# HV_SNS_V0_1.net
KiCad netlist of a schematic drawn in EAGLE
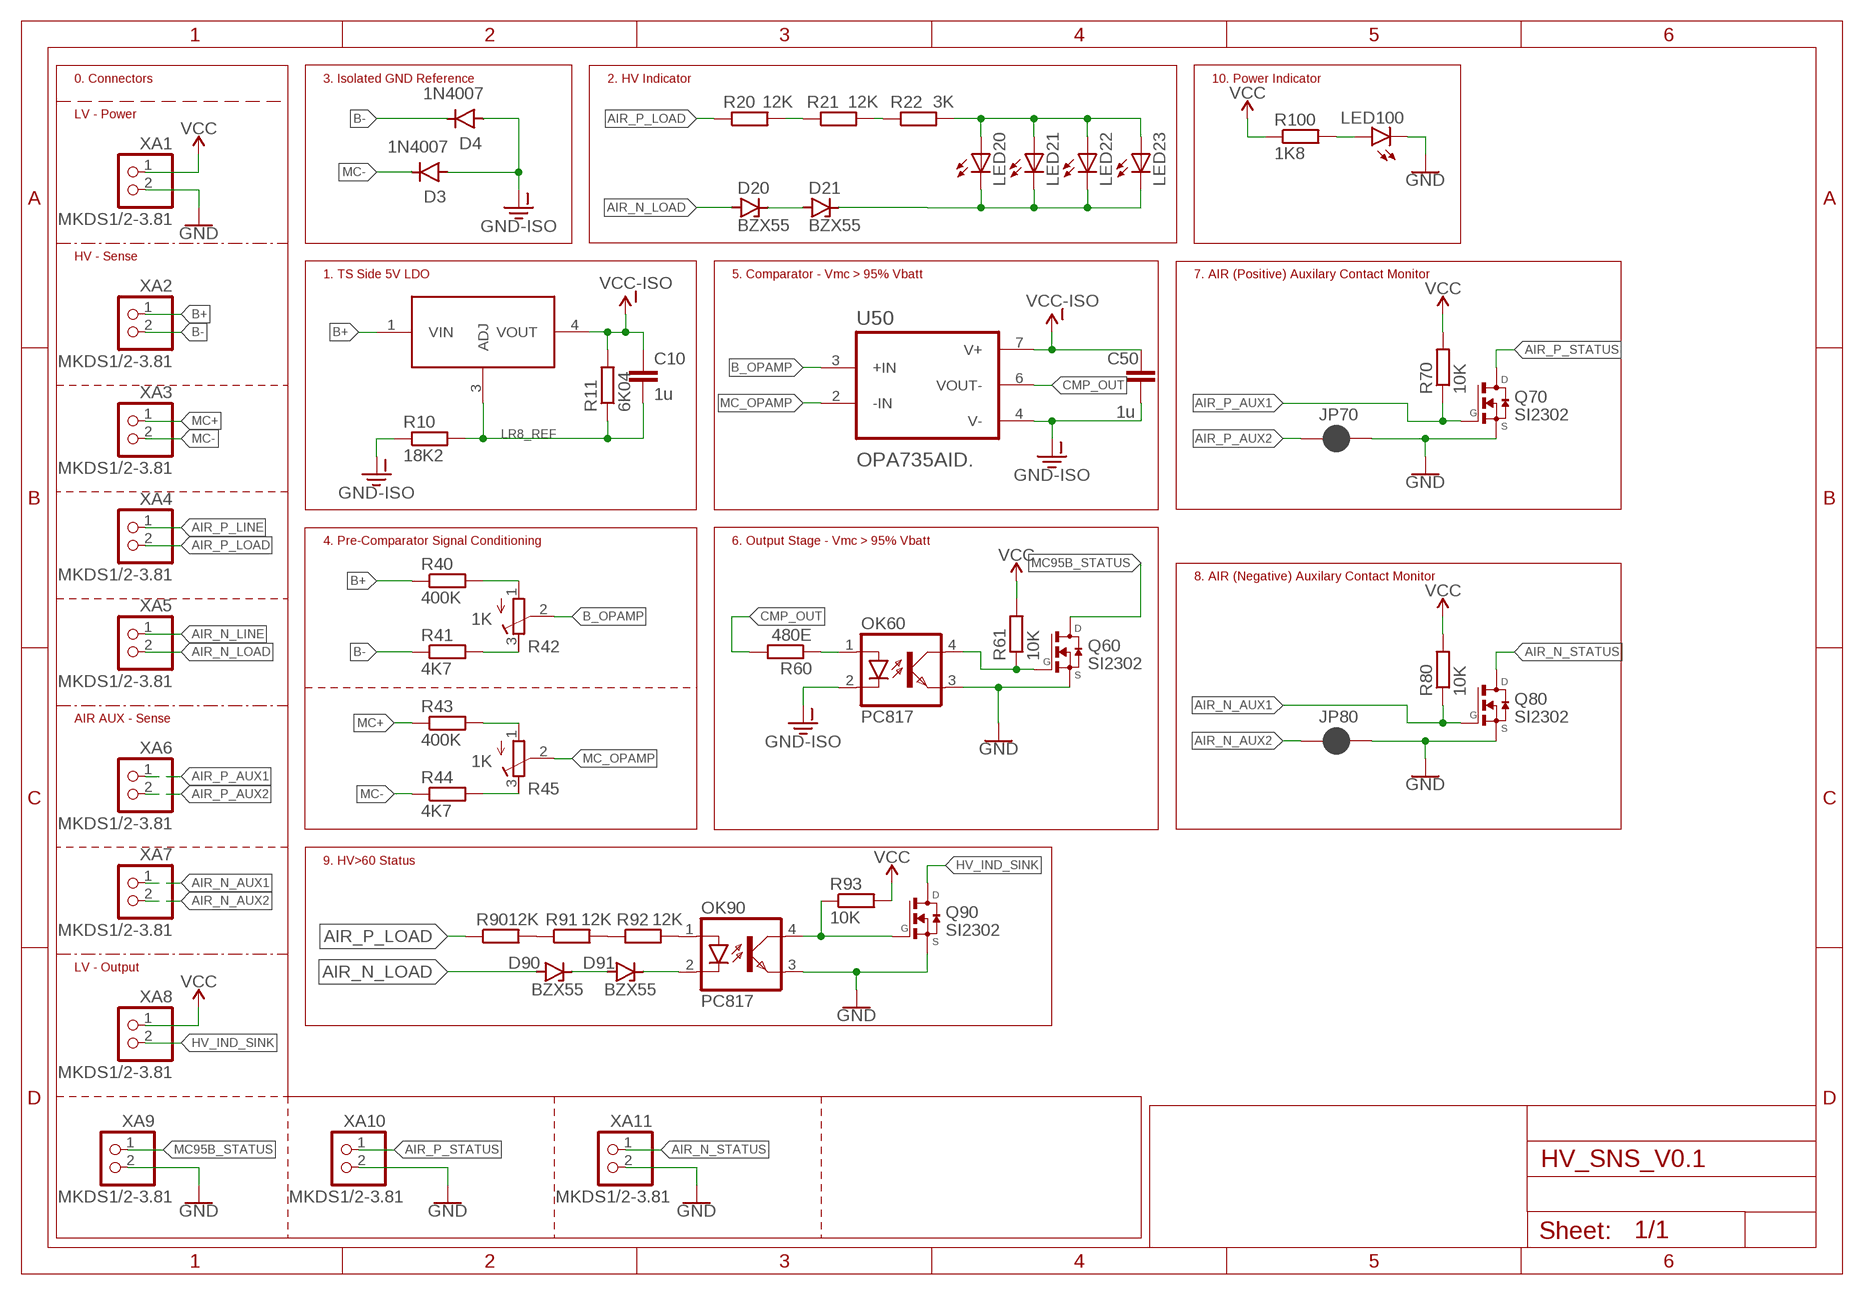
[diagram p0: schematic, sheet 1]

(export (version "E")
  (design (tool "Eeschema 10.0.6"))
  (components
    (comp (ref "C10")
      (value "1u")
      (footprint "eagle-import:C0805")
      (libsource (lib "eagle-import") (part "C-EUC0805"))
    )
    (comp (ref "C50")
      (value "1u")
      (footprint "eagle-import:C0805")
      (libsource (lib "eagle-import") (part "C-EUC0805"))
    )
    (comp (ref "D3")
      (value "1N4007")
      (footprint "eagle-import:DO-41")
      (fields
        (field (name "DIGIKEY_PART_NUMBER") "1N4007MSCT-ND")
        (field (name "MANUFACTURER") "Micro Commercial Co")
        (field (name "CREATED_BY") "PCBLayout.com")
      )
      (libsource (lib "eagle-import") (part "1N4007"))
    )
    (comp (ref "D4")
      (value "1N4007")
      (footprint "eagle-import:DO-41")
      (fields
        (field (name "DIGIKEY_PART_NUMBER") "1N4007MSCT-ND")
        (field (name "MANUFACTURER") "Micro Commercial Co")
        (field (name "CREATED_BY") "PCBLayout.com")
      )
      (libsource (lib "eagle-import") (part "1N4007"))
    )
    (comp (ref "D20")
      (value "BZX55")
      (footprint "eagle-import:DO35Z10")
      (libsource (lib "eagle-import") (part "BZX55"))
    )
    (comp (ref "D21")
      (value "BZX55")
      (footprint "eagle-import:DO35Z10")
      (libsource (lib "eagle-import") (part "BZX55"))
    )
    (comp (ref "D90")
      (value "BZX55")
      (footprint "eagle-import:DO35Z10")
      (libsource (lib "eagle-import") (part "BZX55"))
    )
    (comp (ref "D91")
      (value "BZX55")
      (footprint "eagle-import:DO35Z10")
      (libsource (lib "eagle-import") (part "BZX55"))
    )
    (comp (ref "JP70")
      (value "JUMPER-SMT_2_NC_PASTE_SILK")
      (footprint "eagle-import:SMT-JUMPER_2_NC_PASTE_SILK")
      (libsource (lib "eagle-import") (part "JUMPER-SMT_2_NC_PASTE_SILK"))
    )
    (comp (ref "JP80")
      (value "JUMPER-SMT_2_NC_PASTE_SILK")
      (footprint "eagle-import:SMT-JUMPER_2_NC_PASTE_SILK")
      (libsource (lib "eagle-import") (part "JUMPER-SMT_2_NC_PASTE_SILK"))
    )
    (comp (ref "LED20")
      (value "LED5MM")
      (footprint "eagle-import:LED5MM")
      (libsource (lib "eagle-import") (part "LED5MM"))
    )
    (comp (ref "LED21")
      (value "LED5MM")
      (footprint "eagle-import:LED5MM")
      (libsource (lib "eagle-import") (part "LED5MM"))
    )
    (comp (ref "LED22")
      (value "LED5MM")
      (footprint "eagle-import:LED5MM")
      (libsource (lib "eagle-import") (part "LED5MM"))
    )
    (comp (ref "LED23")
      (value "LED5MM")
      (footprint "eagle-import:LED5MM")
      (libsource (lib "eagle-import") (part "LED5MM"))
    )
    (comp (ref "LED100")
      (value "LEDCHIP-LED0805")
      (footprint "eagle-import:CHIP-LED0805")
      (libsource (lib "eagle-import") (part "led_259_LEDCHIP-LED0805"))
    )
    (comp (ref "OK60")
      (value "PC817")
      (footprint "eagle-import:DIL04")
      (fields (field (name "MPN") "PC817X4J000F"))
      (libsource (lib "eagle-import") (part "PC817"))
    )
    (comp (ref "OK90")
      (value "PC817")
      (footprint "eagle-import:DIL04")
      (fields (field (name "MPN") "PC817X4J000F"))
      (libsource (lib "eagle-import") (part "PC817"))
    )
    (comp (ref "Q60")
      (value "SI2302")
      (footprint "eagle-import:SOT23")
      (fields (field (name "MF") "Vishay Siliconix"))
      (libsource (lib "eagle-import") (part "SI2302"))
    )
    (comp (ref "Q70")
      (value "SI2302")
      (footprint "eagle-import:SOT23")
      (fields (field (name "MF") "Vishay Siliconix"))
      (libsource (lib "eagle-import") (part "SI2302"))
    )
    (comp (ref "Q80")
      (value "SI2302")
      (footprint "eagle-import:SOT23")
      (fields (field (name "MF") "Vishay Siliconix"))
      (libsource (lib "eagle-import") (part "SI2302"))
    )
    (comp (ref "Q90")
      (value "SI2302")
      (footprint "eagle-import:SOT23")
      (fields (field (name "MF") "Vishay Siliconix"))
      (libsource (lib "eagle-import") (part "SI2302"))
    )
    (comp (ref "R10")
      (value "18K2")
      (footprint "eagle-import:R0805")
      (libsource (lib "eagle-import") (part "R-EU_R0805"))
    )
    (comp (ref "R11")
      (value "6K04")
      (footprint "eagle-import:R0805")
      (libsource (lib "eagle-import") (part "R-EU_R0805"))
    )
    (comp (ref "R20")
      (value "12K")
      (footprint "eagle-import:0207_10")
      (libsource (lib "eagle-import") (part "R-EU_0207/10"))
    )
    (comp (ref "R21")
      (value "12K")
      (footprint "eagle-import:0207_10")
      (libsource (lib "eagle-import") (part "R-EU_0207/10"))
    )
    (comp (ref "R22")
      (value "3K")
      (footprint "eagle-import:0207_10")
      (libsource (lib "eagle-import") (part "R-EU_0207/10"))
    )
    (comp (ref "R40")
      (value "400K")
      (footprint "eagle-import:0207_10")
      (libsource (lib "eagle-import") (part "R-EU_0207/10"))
    )
    (comp (ref "R41")
      (value "4K7")
      (footprint "eagle-import:0207_10")
      (libsource (lib "eagle-import") (part "R-EU_0207/10"))
    )
    (comp (ref "R42")
      (value "1K")
      (footprint "eagle-import:RTRIM3296W")
      (libsource (lib "eagle-import") (part "R-TRIMM3296W"))
    )
    (comp (ref "R43")
      (value "400K")
      (footprint "eagle-import:0207_10")
      (libsource (lib "eagle-import") (part "R-EU_0207/10"))
    )
    (comp (ref "R44")
      (value "4K7")
      (footprint "eagle-import:0207_10")
      (libsource (lib "eagle-import") (part "R-EU_0207/10"))
    )
    (comp (ref "R45")
      (value "1K")
      (footprint "eagle-import:RTRIM3296W")
      (libsource (lib "eagle-import") (part "R-TRIMM3296W"))
    )
    (comp (ref "R60")
      (value "480E")
      (footprint "eagle-import:R0805")
      (libsource (lib "eagle-import") (part "R-EU_R0805"))
    )
    (comp (ref "R61")
      (value "10K")
      (footprint "eagle-import:R0805")
      (libsource (lib "eagle-import") (part "R-EU_R0805"))
    )
    (comp (ref "R70")
      (value "10K")
      (footprint "eagle-import:R0805")
      (libsource (lib "eagle-import") (part "R-EU_R0805"))
    )
    (comp (ref "R80")
      (value "10K")
      (footprint "eagle-import:R0805")
      (libsource (lib "eagle-import") (part "R-EU_R0805"))
    )
    (comp (ref "R90")
      (value "12K")
      (footprint "eagle-import:0207_10")
      (libsource (lib "eagle-import") (part "R-EU_0207/10"))
    )
    (comp (ref "R91")
      (value "12K")
      (footprint "eagle-import:0207_10")
      (libsource (lib "eagle-import") (part "R-EU_0207/10"))
    )
    (comp (ref "R92")
      (value "12K")
      (footprint "eagle-import:0207_10")
      (libsource (lib "eagle-import") (part "R-EU_0207/10"))
    )
    (comp (ref "R93")
      (value "10K")
      (footprint "eagle-import:R0805")
      (libsource (lib "eagle-import") (part "R-EU_R0805"))
    )
    (comp (ref "R100")
      (value "1K8")
      (footprint "eagle-import:R0805")
      (libsource (lib "eagle-import") (part "R-EU_R0805"))
    )
    (comp (ref "U10")
      (value "LR8K4-G")
      (footprint "eagle-import:PMX42_DPAK")
      (libsource (lib "eagle-import") (part "LR8K4-G"))
    )
    (comp (ref "U50")
      (value "OPA735AID.")
      (footprint "eagle-import:SO-8")
      (libsource (lib "eagle-import") (part "OPA735AID."))
    )
    (comp (ref "XA1")
      (value "MKDS1/2-3.81")
      (footprint "eagle-import:PHOENIX_MKDS1_2-3.81")
      (fields (field (name "MF") "Phoenix Contact") (field (name "MP") "MKDS 1/ 2-3.81"))
      (libsource (lib "eagle-import") (part "MKDS1/2-3.81"))
    )
    (comp (ref "XA2")
      (value "MKDS1/2-3.81")
      (footprint "eagle-import:PHOENIX_MKDS1_2-3.81")
      (fields (field (name "MF") "Phoenix Contact") (field (name "MP") "MKDS 1/ 2-3.81"))
      (libsource (lib "eagle-import") (part "MKDS1/2-3.81"))
    )
    (comp (ref "XA3")
      (value "MKDS1/2-3.81")
      (footprint "eagle-import:PHOENIX_MKDS1_2-3.81")
      (fields (field (name "MF") "Phoenix Contact") (field (name "MP") "MKDS 1/ 2-3.81"))
      (libsource (lib "eagle-import") (part "MKDS1/2-3.81"))
    )
    (comp (ref "XA4")
      (value "MKDS1/2-3.81")
      (footprint "eagle-import:PHOENIX_MKDS1_2-3.81")
      (fields (field (name "MF") "Phoenix Contact") (field (name "MP") "MKDS 1/ 2-3.81"))
      (libsource (lib "eagle-import") (part "MKDS1/2-3.81"))
    )
    (comp (ref "XA5")
      (value "MKDS1/2-3.81")
      (footprint "eagle-import:PHOENIX_MKDS1_2-3.81")
      (fields (field (name "MF") "Phoenix Contact") (field (name "MP") "MKDS 1/ 2-3.81"))
      (libsource (lib "eagle-import") (part "MKDS1/2-3.81"))
    )
    (comp (ref "XA6")
      (value "MKDS1/2-3.81")
      (footprint "eagle-import:PHOENIX_MKDS1_2-3.81")
      (fields (field (name "MF") "Phoenix Contact") (field (name "MP") "MKDS 1/ 2-3.81"))
      (libsource (lib "eagle-import") (part "MKDS1/2-3.81"))
    )
    (comp (ref "XA7")
      (value "MKDS1/2-3.81")
      (footprint "eagle-import:PHOENIX_MKDS1_2-3.81")
      (fields (field (name "MF") "Phoenix Contact") (field (name "MP") "MKDS 1/ 2-3.81"))
      (libsource (lib "eagle-import") (part "MKDS1/2-3.81"))
    )
    (comp (ref "XA8")
      (value "MKDS1/2-3.81")
      (footprint "eagle-import:PHOENIX_MKDS1_2-3.81")
      (fields (field (name "MF") "Phoenix Contact") (field (name "MP") "MKDS 1/ 2-3.81"))
      (libsource (lib "eagle-import") (part "MKDS1/2-3.81"))
    )
    (comp (ref "XA9")
      (value "MKDS1/2-3.81")
      (footprint "eagle-import:PHOENIX_MKDS1_2-3.81")
      (fields (field (name "MF") "Phoenix Contact") (field (name "MP") "MKDS 1/ 2-3.81"))
      (libsource (lib "eagle-import") (part "MKDS1/2-3.81"))
    )
    (comp (ref "XA10")
      (value "MKDS1/2-3.81")
      (footprint "eagle-import:PHOENIX_MKDS1_2-3.81")
      (fields (field (name "MF") "Phoenix Contact") (field (name "MP") "MKDS 1/ 2-3.81"))
      (libsource (lib "eagle-import") (part "MKDS1/2-3.81"))
    )
    (comp (ref "XA11")
      (value "MKDS1/2-3.81")
      (footprint "eagle-import:PHOENIX_MKDS1_2-3.81")
      (fields (field (name "MF") "Phoenix Contact") (field (name "MP") "MKDS 1/ 2-3.81"))
      (libsource (lib "eagle-import") (part "MKDS1/2-3.81"))
    )
  )
  (nets
    (net (code "1") (name "/LR8_REF") (class "Default")
      (node (ref "C10") (pin "2") (pinfunction "2_2") (pintype "passive"))
      (node (ref "R10") (pin "2") (pinfunction "2_2") (pintype "passive"))
      (node (ref "R11") (pin "1") (pinfunction "1_1") (pintype "passive"))
      (node (ref "U10") (pin "3") (pinfunction "ADJ_3") (pintype "power_in"))
    )
    (net (code "2") (name "AIR_N_AUX1") (class "Default")
      (node (ref "Q80") (pin "1") (pinfunction "G_1") (pintype "passive"))
      (node (ref "R80") (pin "1") (pinfunction "1_1") (pintype "passive"))
      (node (ref "XA7") (pin "1") (pinfunction "1_1") (pintype "passive"))
    )
    (net (code "3") (name "AIR_N_AUX2") (class "Default")
      (node (ref "JP80") (pin "1") (pinfunction "1_1") (pintype "passive"))
      (node (ref "XA7") (pin "2") (pinfunction "2_2") (pintype "passive"))
    )
    (net (code "4") (name "AIR_N_LINE") (class "Default")
      (node (ref "XA5") (pin "1") (pinfunction "1_1") (pintype "passive"))
    )
    (net (code "5") (name "AIR_N_LOAD") (class "Default")
      (node (ref "D20") (pin "A") (pinfunction "A_A") (pintype "passive"))
      (node (ref "D90") (pin "A") (pinfunction "A_A") (pintype "passive"))
      (node (ref "XA5") (pin "2") (pinfunction "2_2") (pintype "passive"))
    )
    (net (code "6") (name "AIR_N_STATUS") (class "Default")
      (node (ref "Q80") (pin "3") (pinfunction "D_3") (pintype "passive"))
      (node (ref "XA11") (pin "1") (pinfunction "1_1") (pintype "passive"))
    )
    (net (code "7") (name "AIR_P_AUX1") (class "Default")
      (node (ref "Q70") (pin "1") (pinfunction "G_1") (pintype "passive"))
      (node (ref "R70") (pin "1") (pinfunction "1_1") (pintype "passive"))
      (node (ref "XA6") (pin "1") (pinfunction "1_1") (pintype "passive"))
    )
    (net (code "8") (name "AIR_P_AUX2") (class "Default")
      (node (ref "JP70") (pin "1") (pinfunction "1_1") (pintype "passive"))
      (node (ref "XA6") (pin "2") (pinfunction "2_2") (pintype "passive"))
    )
    (net (code "9") (name "AIR_P_LINE") (class "Default")
      (node (ref "XA4") (pin "1") (pinfunction "1_1") (pintype "passive"))
    )
    (net (code "10") (name "AIR_P_LOAD") (class "Default")
      (node (ref "R20") (pin "1") (pinfunction "1_1") (pintype "passive"))
      (node (ref "R90") (pin "1") (pinfunction "1_1") (pintype "passive"))
      (node (ref "XA4") (pin "2") (pinfunction "2_2") (pintype "passive"))
    )
    (net (code "11") (name "AIR_P_STATUS") (class "Default")
      (node (ref "Q70") (pin "3") (pinfunction "D_3") (pintype "passive"))
      (node (ref "XA10") (pin "1") (pinfunction "1_1") (pintype "passive"))
    )
    (net (code "12") (name "B+") (class "Default")
      (node (ref "R40") (pin "1") (pinfunction "1_1") (pintype "passive"))
      (node (ref "U10") (pin "1") (pinfunction "VIN_1") (pintype "power_in"))
      (node (ref "XA2") (pin "1") (pinfunction "1_1") (pintype "passive"))
    )
    (net (code "13") (name "B-") (class "Default")
      (node (ref "D4") (pin "C") (pinfunction "C_C") (pintype "passive"))
      (node (ref "R41") (pin "1") (pinfunction "1_1") (pintype "passive"))
      (node (ref "XA2") (pin "2") (pinfunction "2_2") (pintype "passive"))
    )
    (net (code "14") (name "B_OPAMP") (class "Default")
      (node (ref "R42") (pin "2") (pinfunction "S_2") (pintype "passive"))
      (node (ref "U50") (pin "3") (pinfunction "+IN_3") (pintype "input"))
    )
    (net (code "15") (name "CMP_OUT") (class "Default")
      (node (ref "R60") (pin "2") (pinfunction "2_2") (pintype "passive"))
      (node (ref "U50") (pin "6") (pinfunction "VOUT-_6") (pintype "output"))
    )
    (net (code "16") (name "GND") (class "Default")
      (node (ref "JP70") (pin "2") (pinfunction "2_2") (pintype "passive"))
      (node (ref "JP80") (pin "2") (pinfunction "2_2") (pintype "passive"))
      (node (ref "LED100") (pin "C") (pinfunction "C_C") (pintype "passive"))
      (node (ref "OK60") (pin "3") (pinfunction "EMIT_3") (pintype "passive"))
      (node (ref "OK90") (pin "3") (pinfunction "EMIT_3") (pintype "passive"))
      (node (ref "Q60") (pin "2") (pinfunction "S_2") (pintype "passive"))
      (node (ref "Q70") (pin "2") (pinfunction "S_2") (pintype "passive"))
      (node (ref "Q80") (pin "2") (pinfunction "S_2") (pintype "passive"))
      (node (ref "Q90") (pin "2") (pinfunction "S_2") (pintype "passive"))
      (node (ref "XA1") (pin "2") (pinfunction "2_2") (pintype "passive"))
      (node (ref "XA10") (pin "2") (pinfunction "2_2") (pintype "passive"))
      (node (ref "XA11") (pin "2") (pinfunction "2_2") (pintype "passive"))
      (node (ref "XA9") (pin "2") (pinfunction "2_2") (pintype "passive"))
    )
    (net (code "17") (name "GND-ISO") (class "Default")
      (node (ref "C50") (pin "2") (pinfunction "2_2") (pintype "passive"))
      (node (ref "D3") (pin "A") (pinfunction "A_A") (pintype "passive"))
      (node (ref "D4") (pin "A") (pinfunction "A_A") (pintype "passive"))
      (node (ref "OK60") (pin "2") (pinfunction "C_2") (pintype "passive"))
      (node (ref "R10") (pin "1") (pinfunction "1_1") (pintype "passive"))
      (node (ref "U50") (pin "4") (pinfunction "V-_4") (pintype "power_in"))
    )
    (net (code "18") (name "HV_IND_SINK") (class "Default")
      (node (ref "Q90") (pin "3") (pinfunction "D_3") (pintype "passive"))
      (node (ref "XA8") (pin "2") (pinfunction "2_2") (pintype "passive"))
    )
    (net (code "19") (name "MC+") (class "Default")
      (node (ref "R43") (pin "1") (pinfunction "1_1") (pintype "passive"))
      (node (ref "XA3") (pin "1") (pinfunction "1_1") (pintype "passive"))
    )
    (net (code "20") (name "MC-") (class "Default")
      (node (ref "D3") (pin "C") (pinfunction "C_C") (pintype "passive"))
      (node (ref "R44") (pin "1") (pinfunction "1_1") (pintype "passive"))
      (node (ref "XA3") (pin "2") (pinfunction "2_2") (pintype "passive"))
    )
    (net (code "21") (name "MC95B_STATUS") (class "Default")
      (node (ref "Q60") (pin "3") (pinfunction "D_3") (pintype "passive"))
      (node (ref "XA9") (pin "1") (pinfunction "1_1") (pintype "passive"))
    )
    (net (code "22") (name "MC_OPAMP") (class "Default")
      (node (ref "R45") (pin "2") (pinfunction "S_2") (pintype "passive"))
      (node (ref "U50") (pin "2") (pinfunction "-IN_2") (pintype "input"))
    )
    (net (code "23") (name "Net-(D20-PadC)") (class "Default")
      (node (ref "D20") (pin "C") (pinfunction "C_C") (pintype "passive"))
      (node (ref "D21") (pin "A") (pinfunction "A_A") (pintype "passive"))
    )
    (net (code "24") (name "Net-(D90-PadC)") (class "Default")
      (node (ref "D90") (pin "C") (pinfunction "C_C") (pintype "passive"))
      (node (ref "D91") (pin "A") (pinfunction "A_A") (pintype "passive"))
    )
    (net (code "25") (name "Net-(LED20-C)") (class "Default")
      (node (ref "D21") (pin "C") (pinfunction "C_C") (pintype "passive"))
      (node (ref "LED20") (pin "K") (pinfunction "C_K") (pintype "passive"))
      (node (ref "LED21") (pin "K") (pinfunction "C_K") (pintype "passive"))
      (node (ref "LED22") (pin "K") (pinfunction "C_K") (pintype "passive"))
      (node (ref "LED23") (pin "K") (pinfunction "C_K") (pintype "passive"))
    )
    (net (code "26") (name "Net-(LED20-PadA)") (class "Default")
      (node (ref "LED20") (pin "A") (pinfunction "A_A") (pintype "passive"))
      (node (ref "LED21") (pin "A") (pinfunction "A_A") (pintype "passive"))
      (node (ref "LED22") (pin "A") (pinfunction "A_A") (pintype "passive"))
      (node (ref "LED23") (pin "A") (pinfunction "A_A") (pintype "passive"))
      (node (ref "R22") (pin "2") (pinfunction "2_2") (pintype "passive"))
    )
    (net (code "27") (name "Net-(LED100-PadA)") (class "Default")
      (node (ref "LED100") (pin "A") (pinfunction "A_A") (pintype "passive"))
      (node (ref "R100") (pin "2") (pinfunction "2_2") (pintype "passive"))
    )
    (net (code "28") (name "Net-(OK60-A)") (class "Default")
      (node (ref "OK60") (pin "1") (pinfunction "A_1") (pintype "passive"))
      (node (ref "R60") (pin "1") (pinfunction "1_1") (pintype "passive"))
    )
    (net (code "29") (name "Net-(OK60-COL)") (class "Default")
      (node (ref "OK60") (pin "4") (pinfunction "COL_4") (pintype "passive"))
      (node (ref "Q60") (pin "1") (pinfunction "G_1") (pintype "passive"))
      (node (ref "R61") (pin "1") (pinfunction "1_1") (pintype "passive"))
    )
    (net (code "30") (name "Net-(OK90-A)") (class "Default")
      (node (ref "OK90") (pin "1") (pinfunction "A_1") (pintype "passive"))
      (node (ref "R92") (pin "2") (pinfunction "2_2") (pintype "passive"))
    )
    (net (code "31") (name "Net-(OK90-C)") (class "Default")
      (node (ref "D91") (pin "C") (pinfunction "C_C") (pintype "passive"))
      (node (ref "OK90") (pin "2") (pinfunction "C_2") (pintype "passive"))
    )
    (net (code "32") (name "Net-(OK90-COL)") (class "Default")
      (node (ref "OK90") (pin "4") (pinfunction "COL_4") (pintype "passive"))
      (node (ref "Q90") (pin "1") (pinfunction "G_1") (pintype "passive"))
      (node (ref "R93") (pin "1") (pinfunction "1_1") (pintype "passive"))
    )
    (net (code "33") (name "Net-(R20-Pad2)") (class "Default")
      (node (ref "R20") (pin "2") (pinfunction "2_2") (pintype "passive"))
      (node (ref "R21") (pin "1") (pinfunction "1_1") (pintype "passive"))
    )
    (net (code "34") (name "Net-(R21-Pad2)") (class "Default")
      (node (ref "R21") (pin "2") (pinfunction "2_2") (pintype "passive"))
      (node (ref "R22") (pin "1") (pinfunction "1_1") (pintype "passive"))
    )
    (net (code "35") (name "Net-(R42-A)") (class "Default")
      (node (ref "R40") (pin "2") (pinfunction "2_2") (pintype "passive"))
      (node (ref "R42") (pin "1") (pinfunction "A_1") (pintype "passive"))
    )
    (net (code "36") (name "Net-(R42-E)") (class "Default")
      (node (ref "R41") (pin "2") (pinfunction "2_2") (pintype "passive"))
      (node (ref "R42") (pin "3") (pinfunction "E_3") (pintype "passive"))
    )
    (net (code "37") (name "Net-(R45-A)") (class "Default")
      (node (ref "R43") (pin "2") (pinfunction "2_2") (pintype "passive"))
      (node (ref "R45") (pin "1") (pinfunction "A_1") (pintype "passive"))
    )
    (net (code "38") (name "Net-(R45-E)") (class "Default")
      (node (ref "R44") (pin "2") (pinfunction "2_2") (pintype "passive"))
      (node (ref "R45") (pin "3") (pinfunction "E_3") (pintype "passive"))
    )
    (net (code "39") (name "Net-(R90-Pad2)") (class "Default")
      (node (ref "R90") (pin "2") (pinfunction "2_2") (pintype "passive"))
      (node (ref "R91") (pin "1") (pinfunction "1_1") (pintype "passive"))
    )
    (net (code "40") (name "Net-(R91-Pad2)") (class "Default")
      (node (ref "R91") (pin "2") (pinfunction "2_2") (pintype "passive"))
      (node (ref "R92") (pin "1") (pinfunction "1_1") (pintype "passive"))
    )
    (net (code "41") (name "VCC") (class "Default")
      (node (ref "R100") (pin "1") (pinfunction "1_1") (pintype "passive"))
      (node (ref "R61") (pin "2") (pinfunction "2_2") (pintype "passive"))
      (node (ref "R70") (pin "2") (pinfunction "2_2") (pintype "passive"))
      (node (ref "R80") (pin "2") (pinfunction "2_2") (pintype "passive"))
      (node (ref "R93") (pin "2") (pinfunction "2_2") (pintype "passive"))
      (node (ref "XA1") (pin "1") (pinfunction "1_1") (pintype "passive"))
      (node (ref "XA8") (pin "1") (pinfunction "1_1") (pintype "passive"))
    )
    (net (code "42") (name "VCC-ISO") (class "Default")
      (node (ref "C10") (pin "1") (pinfunction "1_1") (pintype "passive"))
      (node (ref "C50") (pin "1") (pinfunction "1_1") (pintype "passive"))
      (node (ref "R11") (pin "2") (pinfunction "2_2") (pintype "passive"))
      (node (ref "U10") (pin "4") (pinfunction "VOUT_4") (pintype "power_in"))
      (node (ref "U50") (pin "7") (pinfunction "V+_7") (pintype "power_in"))
    )
  )
)
